# MeasInUI.net
KiCad netlist of a schematic drawn in Altium Designer
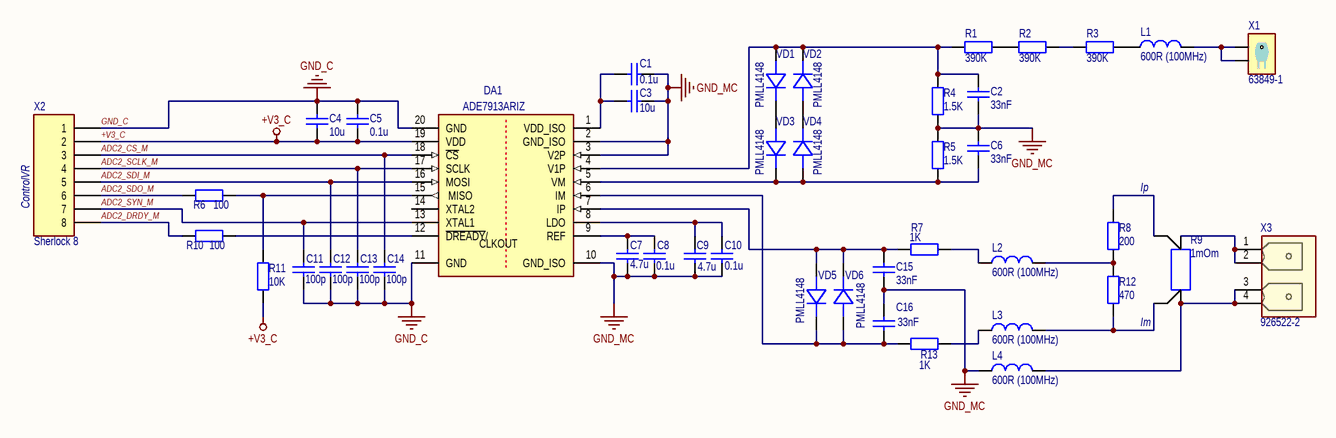
[diagram p0: MeasInUI.SchDoc]

(export (version "E")
  (design (tool "Eeschema 10.0.6"))
  (components
    (comp (ref "C1")
      (value "0.1u")
      (footprint "mainLib:SMD_C_0603")
      (description "SMD C 0603 MURATA 50V 10% X7R")
      (fields (field (name "PARTNUMBER") "GRM188R71H104K") (field (name "MANUFACTURER") "MURATA"))
      (libsource (lib "mainRCLib") (part "C0603 0.1u 50V 10%"))
    )
    (comp (ref "C2")
      (value "33nF")
      (footprint "mainLib:SMD_C_0603")
      (description "SMD C 0603 MURATA 50V 10% X7R")
      (fields (field (name "PARTNUMBER") "GCM188R71H333KA55#") (field (name "MANUFACTURER") "MURATA"))
      (libsource (lib "mainRCLib") (part "C0603 33nF 50V 10%"))
    )
    (comp (ref "C3")
      (value "10u")
      (footprint "mainLib:SMD_C_1206")
      (description "SMD C 1206 MURATA 25V 20% X5R")
      (fields (field (name "PARTNUMBER") "GRM31MR61E106M") (field (name "MANUFACTURER") "MURATA"))
      (libsource (lib "mainRCLib") (part "C1206 10u 25V 20%"))
    )
    (comp (ref "C4")
      (value "10u")
      (footprint "mainLib:SMD_C_1206")
      (description "SMD C 1206 MURATA 25V 20% X5R")
      (fields (field (name "PARTNUMBER") "GRM31MR61E106M") (field (name "MANUFACTURER") "MURATA"))
      (libsource (lib "mainRCLib") (part "C1206 10u 25V 20%"))
    )
    (comp (ref "C5")
      (value "0.1u")
      (footprint "mainLib:SMD_C_0603")
      (description "SMD C 0603 MURATA 50V 10% X7R")
      (fields (field (name "PARTNUMBER") "GRM188R71H104K") (field (name "MANUFACTURER") "MURATA"))
      (libsource (lib "mainRCLib") (part "C0603 0.1u 50V 10%"))
    )
    (comp (ref "C6")
      (value "33nF")
      (footprint "mainLib:SMD_C_0603")
      (description "SMD C 0603 MURATA 50V 10% X7R")
      (fields (field (name "PARTNUMBER") "GCM188R71H333KA55#") (field (name "MANUFACTURER") "MURATA"))
      (libsource (lib "mainRCLib") (part "C0603 33nF 50V 10%"))
    )
    (comp (ref "C7")
      (value "4.7u")
      (footprint "mainLib:SMD_C_0805")
      (description "SMD C 0805 MURATA 50V 5% NP0")
      (fields (field (name "PARTNUMBER") "GRM21BR61E475M") (field (name "MANUFACTURER") "MURATA"))
      (libsource (lib "mainRCLib") (part "C0805 4.7u 25V 20%  X5R"))
    )
    (comp (ref "C8")
      (value "0.1u")
      (footprint "mainLib:SMD_C_0603")
      (description "SMD C 0603 MURATA 50V 10% X7R")
      (fields (field (name "PARTNUMBER") "GRM188R71H104K") (field (name "MANUFACTURER") "MURATA"))
      (libsource (lib "mainRCLib") (part "C0603 0.1u 50V 10%"))
    )
    (comp (ref "C9")
      (value "4.7u")
      (footprint "mainLib:SMD_C_0805")
      (description "SMD C 0805 MURATA 50V 5% NP0")
      (fields (field (name "PARTNUMBER") "GRM21BR61E475M") (field (name "MANUFACTURER") "MURATA"))
      (libsource (lib "mainRCLib") (part "C0805 4.7u 25V 20%  X5R"))
    )
    (comp (ref "C10")
      (value "0.1u")
      (footprint "mainLib:SMD_C_0603")
      (description "SMD C 0603 MURATA 50V 10% X7R")
      (fields (field (name "PARTNUMBER") "GRM188R71H104K") (field (name "MANUFACTURER") "MURATA"))
      (libsource (lib "mainRCLib") (part "C0603 0.1u 50V 10%"))
    )
    (comp (ref "C11")
      (value "100p")
      (footprint "mainLib:SMD_C_0603")
      (description "SMD C 0603 MURATA 100V 5% NP0")
      (fields (field (name "PARTNUMBER") "GRM1885C2A101JA01") (field (name "MANUFACTURER") "MURATA"))
      (libsource (lib "mainRCLib") (part "C0603 100p 100V 5%"))
    )
    (comp (ref "C12")
      (value "100p")
      (footprint "mainLib:SMD_C_0603")
      (description "SMD C 0603 MURATA 100V 5% NP0")
      (fields (field (name "PARTNUMBER") "GRM1885C2A101JA01") (field (name "MANUFACTURER") "MURATA"))
      (libsource (lib "mainRCLib") (part "C0603 100p 100V 5%"))
    )
    (comp (ref "C13")
      (value "100p")
      (footprint "mainLib:SMD_C_0603")
      (description "SMD C 0603 MURATA 100V 5% NP0")
      (fields (field (name "PARTNUMBER") "GRM1885C2A101JA01") (field (name "MANUFACTURER") "MURATA"))
      (libsource (lib "mainRCLib") (part "C0603 100p 100V 5%"))
    )
    (comp (ref "C14")
      (value "100p")
      (footprint "mainLib:SMD_C_0603")
      (description "SMD C 0603 MURATA 100V 5% NP0")
      (fields (field (name "PARTNUMBER") "GRM1885C2A101JA01") (field (name "MANUFACTURER") "MURATA"))
      (libsource (lib "mainRCLib") (part "C0603 100p 100V 5%"))
    )
    (comp (ref "C15")
      (value "33nF")
      (footprint "mainLib:SMD_C_0603")
      (description "SMD C 0603 MURATA 50V 10% X7R")
      (fields (field (name "PARTNUMBER") "GCM188R71H333KA55#") (field (name "MANUFACTURER") "MURATA"))
      (libsource (lib "mainRCLib") (part "C0603 33nF 50V 10%"))
    )
    (comp (ref "C16")
      (value "33nF")
      (footprint "mainLib:SMD_C_0603")
      (description "SMD C 0603 MURATA 50V 10% X7R")
      (fields (field (name "PARTNUMBER") "GCM188R71H333KA55#") (field (name "MANUFACTURER") "MURATA"))
      (libsource (lib "mainRCLib") (part "C0603 33nF 50V 10%"))
    )
    (comp (ref "DA1")
      (value "ADE7913ARIZ")
      (footprint "mainLib:SOIC-20 WidBody (RI-20-1)")
      (description "Isolated, Sigma-Delta ADC with SPI")
      (fields (field (name "MANUFACTURER") "Analog Device"))
      (libsource (lib "mainLib") (part "ADE7913ARIZ"))
    )
    (comp (ref "L1")
      (value "600R (100MHz)")
      (footprint "mainLib:SMD_L_1206")
      (description "600R 1.5A (100MHz)")
      (fields (field (name "MANUFACTURER") "TDK") (field (name "PARTNUMBER") "BLM31PG601SN1"))
      (libsource (lib "mainLib") (part "BLM31PG601SN1"))
    )
    (comp (ref "L2")
      (value "600R (100MHz)")
      (footprint "mainLib:SMD_L_1206")
      (description "600R 1.5A (100MHz)")
      (fields (field (name "MANUFACTURER") "TDK") (field (name "PARTNUMBER") "BLM31PG601SN1"))
      (libsource (lib "mainLib") (part "BLM31PG601SN1"))
    )
    (comp (ref "L3")
      (value "600R (100MHz)")
      (footprint "mainLib:SMD_L_1206")
      (description "600R 1.5A (100MHz)")
      (fields (field (name "MANUFACTURER") "TDK") (field (name "PARTNUMBER") "BLM31PG601SN1"))
      (libsource (lib "mainLib") (part "BLM31PG601SN1"))
    )
    (comp (ref "L4")
      (value "600R (100MHz)")
      (footprint "mainLib:SMD_L_1206")
      (description "600R 1.5A (100MHz)")
      (fields (field (name "MANUFACTURER") "TDK") (field (name "PARTNUMBER") "BLM31PG601SN1"))
      (libsource (lib "mainLib") (part "BLM31PG601SN1"))
    )
    (comp (ref "R1")
      (value "390K")
      (footprint "mainLib:SMD_R_1206")
      (description "SMD R 1206 VISHAY 0.25W 200V 1% 100ppm")
      (fields (field (name "PARTNUMBER") "CRCW1206390KFK") (field (name "MANUFACTURER") "VISHAY"))
      (libsource (lib "mainRCLib") (part "R1206 390K 1%"))
    )
    (comp (ref "R2")
      (value "390K")
      (footprint "mainLib:SMD_R_1206")
      (description "SMD R 1206 VISHAY 0.25W 200V 1% 100ppm")
      (fields (field (name "PARTNUMBER") "CRCW1206390KFK") (field (name "MANUFACTURER") "VISHAY"))
      (libsource (lib "mainRCLib") (part "R1206 390K 1%"))
    )
    (comp (ref "R3")
      (value "390K")
      (footprint "mainLib:SMD_R_1206")
      (description "SMD R 1206 VISHAY 0.25W 200V 1% 100ppm")
      (fields (field (name "PARTNUMBER") "CRCW1206390KFK") (field (name "MANUFACTURER") "VISHAY"))
      (libsource (lib "mainRCLib") (part "R1206 390K 1%"))
    )
    (comp (ref "R4")
      (value "1.5K")
      (footprint "mainLib:SMD_R_1206")
      (description "SMD R 1206 VISHAY 0.25W 200V 1% 100ppm")
      (fields (field (name "PARTNUMBER") "CRCW12061K50FK") (field (name "MANUFACTURER") "VISHAY"))
      (libsource (lib "mainRCLib") (part "R1206 1.5K 1%"))
    )
    (comp (ref "R5")
      (value "1.5K")
      (footprint "mainLib:SMD_R_1206")
      (description "SMD R 1206 VISHAY 0.25W 200V 1% 100ppm")
      (fields (field (name "PARTNUMBER") "CRCW12061K50FK") (field (name "MANUFACTURER") "VISHAY"))
      (libsource (lib "mainRCLib") (part "R1206 1.5K 1%"))
    )
    (comp (ref "R6")
      (value "100")
      (footprint "SMD_R_0603")
      (description "SMD R 0603 VISHAY 0.1W 75V 1% 100ppm")
      (fields (field (name "PARTNUMBER") "CRCW0603100RFK") (field (name "MANUFACTURER") "VISHAY"))
      (libsource (lib "mainRCLib") (part "R0603 100 1%"))
    )
    (comp (ref "R7")
      (value "1K")
      (footprint "mainLib:SMD_R_0805")
      (description "SMD R 0805 VISHAY 0.125W 150V 1% 100ppm")
      (fields (field (name "PARTNUMBER") "CRCW08051K00FK") (field (name "MANUFACTURER") "VISHAY"))
      (libsource (lib "mainRCLib") (part "R0805 1K 1%"))
    )
    (comp (ref "R8")
      (value "200")
      (footprint "mainLib:SMD_R_0805")
      (description "SMD R 0805 VISHAY 0.125W 150V 1% 100ppm")
      (fields (field (name "PARTNUMBER") "CRCW0805200RFK") (field (name "MANUFACTURER") "VISHAY"))
      (libsource (lib "mainRCLib") (part "R0805 200 1%"))
    )
    (comp (ref "R9")
      (value "1mOm")
      (footprint "mainLib:WSL3637 1mOm")
      (description "WSL3637 1mOm 3W 1% 75ppm")
      (fields (field (name "PARTNUMBER") "WSL36371L000F") (field (name "MANUFACTURER") "Vishay"))
      (libsource (lib "mainLib") (part "WSL3637 1mOm 3W"))
    )
    (comp (ref "R10")
      (value "100")
      (footprint "SMD_R_0603")
      (description "SMD R 0603 VISHAY 0.1W 75V 1% 100ppm")
      (fields (field (name "PARTNUMBER") "CRCW0603100RFK") (field (name "MANUFACTURER") "VISHAY"))
      (libsource (lib "mainRCLib") (part "R0603 100 1%"))
    )
    (comp (ref "R11")
      (value "10K")
      (footprint "SMD_R_0603")
      (description "SMD R 0603 VISHAY 0.1W 75V 1% 100ppm")
      (fields (field (name "PARTNUMBER") "CRCW060310K0FK") (field (name "MANUFACTURER") "VISHAY"))
      (libsource (lib "mainRCLib") (part "R0603 10К 1%"))
    )
    (comp (ref "R12")
      (value "470")
      (footprint "mainLib:SMD_R_0805")
      (description "SMD R 0805 VISHAY 0.125W 150V 1% 100ppm")
      (fields (field (name "PARTNUMBER") "CRCW0805470RFK") (field (name "MANUFACTURER") "VISHAY"))
      (libsource (lib "mainRCLib") (part "R0805 470 1%"))
    )
    (comp (ref "R13")
      (value "1K")
      (footprint "mainLib:SMD_R_0805")
      (description "SMD R 0805 VISHAY 0.125W 150V 1% 100ppm")
      (fields (field (name "PARTNUMBER") "CRCW08051K00FK") (field (name "MANUFACTURER") "VISHAY"))
      (libsource (lib "mainRCLib") (part "R0805 1K 1%"))
    )
    (comp (ref "VD1")
      (value "PMLL4148")
      (footprint "mainLib:SOD80C")
      (description "If=0.2A, Vf=1V Vrrm=100V Diode (SOD80C)")
      (fields (field (name "MANUFACTURER") "NXP Semiconductors"))
      (libsource (lib "mainLib") (part "PMLL4148"))
    )
    (comp (ref "VD2")
      (value "PMLL4148")
      (footprint "mainLib:SOD80C")
      (description "If=0.2A, Vf=1V Vrrm=100V Diode (SOD80C)")
      (fields (field (name "MANUFACTURER") "NXP Semiconductors"))
      (libsource (lib "mainLib") (part "PMLL4148"))
    )
    (comp (ref "VD3")
      (value "PMLL4148")
      (footprint "mainLib:SOD80C")
      (description "If=0.2A, Vf=1V Vrrm=100V Diode (SOD80C)")
      (fields (field (name "MANUFACTURER") "NXP Semiconductors"))
      (libsource (lib "mainLib") (part "PMLL4148"))
    )
    (comp (ref "VD4")
      (value "PMLL4148")
      (footprint "mainLib:SOD80C")
      (description "If=0.2A, Vf=1V Vrrm=100V Diode (SOD80C)")
      (fields (field (name "MANUFACTURER") "NXP Semiconductors"))
      (libsource (lib "mainLib") (part "PMLL4148"))
    )
    (comp (ref "VD5")
      (value "PMLL4148")
      (footprint "mainLib:SOD80C")
      (description "If=0.2A, Vf=1V Vrrm=100V Diode (SOD80C)")
      (fields (field (name "MANUFACTURER") "NXP Semiconductors"))
      (libsource (lib "mainLib") (part "PMLL4148"))
    )
    (comp (ref "VD6")
      (value "PMLL4148")
      (footprint "mainLib:SOD80C")
      (description "If=0.2A, Vf=1V Vrrm=100V Diode (SOD80C)")
      (fields (field (name "MANUFACTURER") "NXP Semiconductors"))
      (libsource (lib "mainLib") (part "PMLL4148"))
    )
    (comp (ref "X1")
      (value "63849-1")
      (footprint "mainLib:63849-1")
      (description "PCB, 6.3х0.8, hole")
      (fields (field (name "MANUFACTURER") "TE Connectivity"))
      (libsource (lib "mainLib") (part "63849-1"))
    )
    (comp (ref "X2")
      (value "Sherlock 8")
      (footprint "mainLib:35362-0850")
      (description "Sherlock 8 Side, 2A 125V 2mm")
      (fields (field (name "PARTNUMBER") "35362-0850") (field (name "MANUFACTURER") "MOLEX"))
      (libsource (lib "mainLib") (part "35362-0850"))
    )
    (comp (ref "X3")
      (value "926522-2")
      (footprint "mainLib:63849-1x2")
      (description "DUAL TAB FASTON PCB (926522-2)")
      (fields (field (name "PARTNUMBER") "63849-1x2") (field (name "MANUFACTURER") "TE Connectivity"))
      (libsource (lib "mainLib") (part "63849-1x2"))
    )
  )
  (nets
    (net (code "1") (name "+V3_C") (class "Default")
      (node (ref "C4") (pin "1") (pinfunction "1_1") (pintype "passive"))
      (node (ref "C5") (pin "1") (pinfunction "1_1") (pintype "passive"))
      (node (ref "DA1") (pin "19") (pinfunction "VDD_19") (pintype "power_in"))
      (node (ref "R11") (pin "1") (pinfunction "1_1") (pintype "passive"))
      (node (ref "X2") (pin "2") (pinfunction "2_2") (pintype "passive"))
    )
    (net (code "2") (name "/ADC2_CS_M") (class "Default")
      (node (ref "C14") (pin "2") (pinfunction "2_2") (pintype "passive"))
      (node (ref "DA1") (pin "18") (pinfunction "~{CS}_18") (pintype "input"))
      (node (ref "X2") (pin "3") (pinfunction "3_3") (pintype "passive"))
    )
    (net (code "3") (name "/ADC2_DRDY_M") (class "Default")
      (node (ref "R10") (pin "1") (pinfunction "1_1") (pintype "passive"))
      (node (ref "X2") (pin "8") (pinfunction "8_8") (pintype "passive"))
    )
    (net (code "4") (name "/ADC2_SCLK_M") (class "Default")
      (node (ref "C13") (pin "2") (pinfunction "2_2") (pintype "passive"))
      (node (ref "DA1") (pin "17") (pinfunction "SCLK_17") (pintype "input"))
      (node (ref "X2") (pin "4") (pinfunction "4_4") (pintype "passive"))
    )
    (net (code "5") (name "/ADC2_SDI_M") (class "Default")
      (node (ref "C12") (pin "2") (pinfunction "2_2") (pintype "passive"))
      (node (ref "DA1") (pin "16") (pinfunction "MOSI_16") (pintype "input"))
      (node (ref "X2") (pin "5") (pinfunction "5_5") (pintype "passive"))
    )
    (net (code "6") (name "/ADC2_SDO_M") (class "Default")
      (node (ref "R6") (pin "1") (pinfunction "1_1") (pintype "passive"))
      (node (ref "X2") (pin "6") (pinfunction "6_6") (pintype "passive"))
    )
    (net (code "7") (name "/ADC2_SYN_M") (class "Default")
      (node (ref "C11") (pin "2") (pinfunction "2_2") (pintype "passive"))
      (node (ref "DA1") (pin "13") (pinfunction "XTAL1_13") (pintype "passive"))
      (node (ref "X2") (pin "7") (pinfunction "7_7") (pintype "passive"))
    )
    (net (code "8") (name "GND_C") (class "Default")
      (node (ref "C11") (pin "1") (pinfunction "1_1") (pintype "passive"))
      (node (ref "C12") (pin "1") (pinfunction "1_1") (pintype "passive"))
      (node (ref "C13") (pin "1") (pinfunction "1_1") (pintype "passive"))
      (node (ref "C14") (pin "1") (pinfunction "1_1") (pintype "passive"))
      (node (ref "C4") (pin "2") (pinfunction "2_2") (pintype "passive"))
      (node (ref "C5") (pin "2") (pinfunction "2_2") (pintype "passive"))
      (node (ref "DA1") (pin "11") (pinfunction "GND_11") (pintype "power_in"))
      (node (ref "DA1") (pin "20") (pinfunction "GND_20") (pintype "power_in"))
      (node (ref "X2") (pin "1") (pinfunction "1_1") (pintype "passive"))
    )
    (net (code "9") (name "GND_MC") (class "Default")
      (node (ref "C1") (pin "1") (pinfunction "1_1") (pintype "passive"))
      (node (ref "C10") (pin "1") (pinfunction "1_1") (pintype "passive"))
      (node (ref "C15") (pin "1") (pinfunction "1_1") (pintype "passive"))
      (node (ref "C16") (pin "2") (pinfunction "2_2") (pintype "passive"))
      (node (ref "C2") (pin "1") (pinfunction "1_1") (pintype "passive"))
      (node (ref "C3") (pin "1") (pinfunction "1_1") (pintype "passive"))
      (node (ref "C6") (pin "2") (pinfunction "2_2") (pintype "passive"))
      (node (ref "C7") (pin "1") (pinfunction "1_1") (pintype "passive"))
      (node (ref "C8") (pin "2") (pinfunction "2_2") (pintype "passive"))
      (node (ref "C9") (pin "1") (pinfunction "1_1") (pintype "passive"))
      (node (ref "DA1") (pin "10") (pinfunction "GND_ISO_10") (pintype "power_in"))
      (node (ref "DA1") (pin "2") (pinfunction "GND_ISO_2") (pintype "power_in"))
      (node (ref "DA1") (pin "3") (pinfunction "V2P_3") (pintype "input"))
      (node (ref "L4") (pin "1") (pinfunction "1_1") (pintype "passive"))
      (node (ref "R4") (pin "1") (pinfunction "1_1") (pintype "passive"))
      (node (ref "R5") (pin "2") (pinfunction "2_2") (pintype "passive"))
    )
    (net (code "10") (name "Net-(DA1-IM)") (class "Default")
      (node (ref "C16") (pin "1") (pinfunction "1_1") (pintype "passive"))
      (node (ref "DA1") (pin "6") (pinfunction "IM_6") (pintype "input"))
      (node (ref "R13") (pin "1") (pinfunction "1_1") (pintype "passive"))
      (node (ref "VD5") (pin "2") (pinfunction "CATHODE_2") (pintype "passive"))
      (node (ref "VD6") (pin "1") (pinfunction "ANODE_1") (pintype "passive"))
    )
    (net (code "11") (name "Net-(DA1-IP)") (class "Default")
      (node (ref "C15") (pin "2") (pinfunction "2_2") (pintype "passive"))
      (node (ref "DA1") (pin "7") (pinfunction "IP_7") (pintype "input"))
      (node (ref "R7") (pin "1") (pinfunction "1_1") (pintype "passive"))
      (node (ref "VD5") (pin "1") (pinfunction "ANODE_1") (pintype "passive"))
      (node (ref "VD6") (pin "2") (pinfunction "CATHODE_2") (pintype "passive"))
    )
    (net (code "12") (name "Net-(DA1-LDO)") (class "Default")
      (node (ref "C10") (pin "2") (pinfunction "2_2") (pintype "passive"))
      (node (ref "C9") (pin "2") (pinfunction "2_2") (pintype "passive"))
      (node (ref "DA1") (pin "8") (pinfunction "LDO_8") (pintype "passive"))
    )
    (net (code "13") (name "Net-(DA1-MISO)") (class "Default")
      (node (ref "DA1") (pin "15") (pinfunction "MISO_15") (pintype "output"))
      (node (ref "R11") (pin "2") (pinfunction "2_2") (pintype "passive"))
      (node (ref "R6") (pin "2") (pinfunction "2_2") (pintype "passive"))
    )
    (net (code "14") (name "Net-(DA1-REF)") (class "Default")
      (node (ref "C7") (pin "2") (pinfunction "2_2") (pintype "passive"))
      (node (ref "C8") (pin "1") (pinfunction "1_1") (pintype "passive"))
      (node (ref "DA1") (pin "9") (pinfunction "REF_9") (pintype "passive"))
    )
    (net (code "15") (name "Net-(DA1-V1P)") (class "Default")
      (node (ref "C2") (pin "2") (pinfunction "2_2") (pintype "passive"))
      (node (ref "DA1") (pin "4") (pinfunction "V1P_4") (pintype "input"))
      (node (ref "R1") (pin "1") (pinfunction "1_1") (pintype "passive"))
      (node (ref "R4") (pin "2") (pinfunction "2_2") (pintype "passive"))
      (node (ref "VD1") (pin "1") (pinfunction "ANODE_1") (pintype "passive"))
      (node (ref "VD2") (pin "2") (pinfunction "CATHODE_2") (pintype "passive"))
    )
    (net (code "16") (name "Net-(DA1-VDD_ISO)") (class "Default")
      (node (ref "C1") (pin "2") (pinfunction "2_2") (pintype "passive"))
      (node (ref "C3") (pin "2") (pinfunction "2_2") (pintype "passive"))
      (node (ref "DA1") (pin "1") (pinfunction "VDD_ISO_1") (pintype "power_in"))
    )
    (net (code "17") (name "Net-(DA1-VM)") (class "Default")
      (node (ref "C6") (pin "1") (pinfunction "1_1") (pintype "passive"))
      (node (ref "DA1") (pin "5") (pinfunction "VM_5") (pintype "input"))
      (node (ref "R5") (pin "1") (pinfunction "1_1") (pintype "passive"))
      (node (ref "VD3") (pin "2") (pinfunction "CATHODE_2") (pintype "passive"))
      (node (ref "VD4") (pin "1") (pinfunction "ANODE_1") (pintype "passive"))
    )
    (net (code "18") (name "Net-(DA1-~{DREADY}{slash})") (class "Default")
      (node (ref "DA1") (pin "12") (pinfunction "~{DREADY}/_12") (pintype "passive"))
      (node (ref "R10") (pin "2") (pinfunction "2_2") (pintype "passive"))
    )
    (net (code "19") (name "Net-(L1-Pad1)") (class "Default")
      (node (ref "L1") (pin "1") (pinfunction "1_1") (pintype "passive"))
      (node (ref "R3") (pin "2") (pinfunction "2_2") (pintype "passive"))
    )
    (net (code "20") (name "Net-(L1-Pad2)") (class "Default")
      (node (ref "L1") (pin "2") (pinfunction "2_2") (pintype "passive"))
      (node (ref "X1") (pin "1") (pinfunction "1_1") (pintype "passive"))
      (node (ref "X1") (pin "2") (pinfunction "2_2") (pintype "passive"))
    )
    (net (code "21") (name "Net-(L2-Pad1)") (class "Default")
      (node (ref "L2") (pin "1") (pinfunction "1_1") (pintype "passive"))
      (node (ref "R7") (pin "2") (pinfunction "2_2") (pintype "passive"))
    )
    (net (code "22") (name "Net-(L2-Pad2)") (class "Default")
      (node (ref "L2") (pin "2") (pinfunction "2_2") (pintype "passive"))
      (node (ref "R12") (pin "2") (pinfunction "2_2") (pintype "passive"))
      (node (ref "R8") (pin "1") (pinfunction "1_1") (pintype "passive"))
    )
    (net (code "23") (name "Net-(L3-Pad1)") (class "Default")
      (node (ref "L3") (pin "1") (pinfunction "1_1") (pintype "passive"))
      (node (ref "R13") (pin "2") (pinfunction "2_2") (pintype "passive"))
    )
    (net (code "24") (name "Net-(R1-Pad2)") (class "Default")
      (node (ref "R1") (pin "2") (pinfunction "2_2") (pintype "passive"))
      (node (ref "R2") (pin "1") (pinfunction "1_1") (pintype "passive"))
    )
    (net (code "25") (name "Net-(R2-Pad2)") (class "Default")
      (node (ref "R2") (pin "2") (pinfunction "2_2") (pintype "passive"))
      (node (ref "R3") (pin "1") (pinfunction "1_1") (pintype "passive"))
    )
    (net (code "26") (name "Net-(R9-E1)") (class "Default")
      (node (ref "L3") (pin "2") (pinfunction "2_2") (pintype "passive"))
      (node (ref "R12") (pin "1") (pinfunction "1_1") (pintype "passive"))
      (node (ref "R9") (pin "2") (pinfunction "E1_2") (pintype "passive"))
    )
    (net (code "27") (name "Net-(R9-E2)") (class "Default")
      (node (ref "R8") (pin "2") (pinfunction "2_2") (pintype "passive"))
      (node (ref "R9") (pin "4") (pinfunction "E2_4") (pintype "passive"))
    )
    (net (code "28") (name "Net-(R9-I1)") (class "Default")
      (node (ref "L4") (pin "2") (pinfunction "2_2") (pintype "passive"))
      (node (ref "R9") (pin "1") (pinfunction "I1_1") (pintype "passive"))
      (node (ref "X3") (pin "3") (pinfunction "3_3") (pintype "passive"))
      (node (ref "X3") (pin "4") (pinfunction "4_4") (pintype "passive"))
    )
    (net (code "29") (name "Net-(R9-I2)") (class "Default")
      (node (ref "R9") (pin "3") (pinfunction "I2_3") (pintype "passive"))
      (node (ref "X3") (pin "1") (pinfunction "1_1") (pintype "passive"))
      (node (ref "X3") (pin "2") (pinfunction "2_2") (pintype "passive"))
    )
    (net (code "30") (name "Net-(VD1-CATHODE)") (class "Default")
      (node (ref "VD1") (pin "2") (pinfunction "CATHODE_2") (pintype "passive"))
      (node (ref "VD3") (pin "1") (pinfunction "ANODE_1") (pintype "passive"))
    )
    (net (code "31") (name "Net-(VD2-ANODE)") (class "Default")
      (node (ref "VD2") (pin "1") (pinfunction "ANODE_1") (pintype "passive"))
      (node (ref "VD4") (pin "2") (pinfunction "CATHODE_2") (pintype "passive"))
    )
    (net (code "32") (name "unconnected-(DA1-XTAL2-Pad14)") (class "Default")
      (node (ref "DA1") (pin "14") (pinfunction "XTAL2_14") (pintype "passive"))
    )
  )
)
